# 35x35.net
KiCad netlist of a schematic drawn in EAGLE
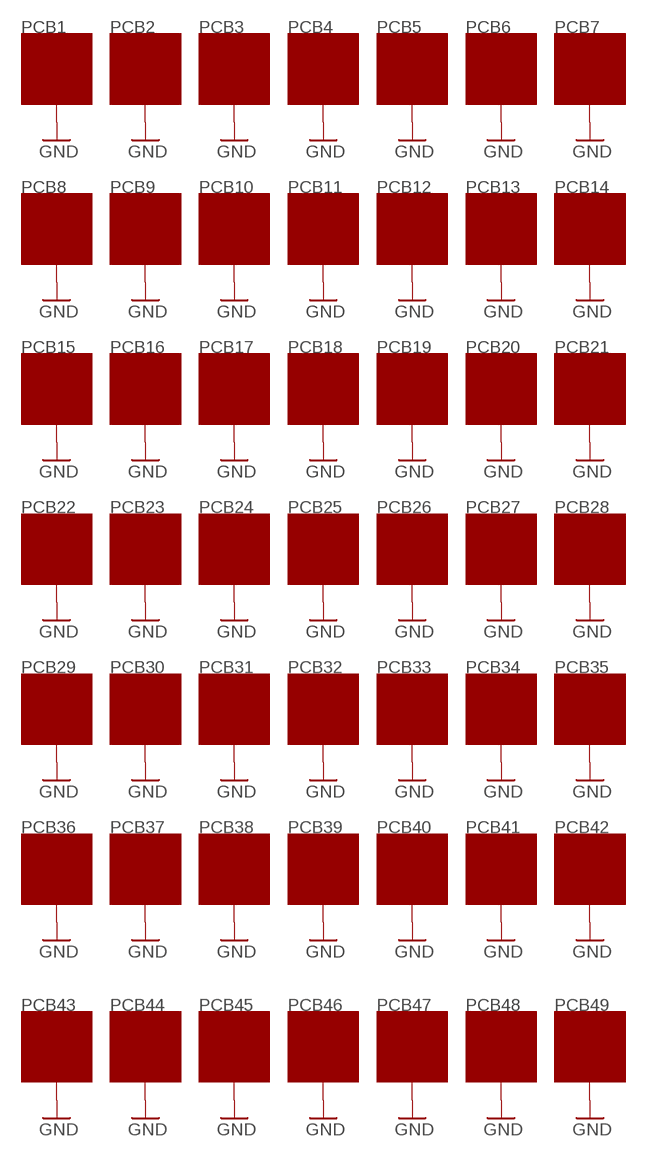
[diagram p0: schematic, sheet 1]

(export (version "E")
  (design (tool "Eeschema 10.0.6"))
  (components
    (comp (ref "PCB1")
      (value "ZZZ_MODULE05X05")
      (footprint "eagle-import:ZZZ_MODULE_05X05")
      (libsource (lib "eagle-import") (part "ZZZ_MODULE05X05"))
    )
    (comp (ref "PCB2")
      (value "ZZZ_MODULE05X05")
      (footprint "eagle-import:ZZZ_MODULE_05X05")
      (libsource (lib "eagle-import") (part "ZZZ_MODULE05X05"))
    )
    (comp (ref "PCB3")
      (value "ZZZ_MODULE05X05")
      (footprint "eagle-import:ZZZ_MODULE_05X05")
      (libsource (lib "eagle-import") (part "ZZZ_MODULE05X05"))
    )
    (comp (ref "PCB4")
      (value "ZZZ_MODULE05X05")
      (footprint "eagle-import:ZZZ_MODULE_05X05")
      (libsource (lib "eagle-import") (part "ZZZ_MODULE05X05"))
    )
    (comp (ref "PCB5")
      (value "ZZZ_MODULE05X05")
      (footprint "eagle-import:ZZZ_MODULE_05X05")
      (libsource (lib "eagle-import") (part "ZZZ_MODULE05X05"))
    )
    (comp (ref "PCB6")
      (value "ZZZ_MODULE05X05")
      (footprint "eagle-import:ZZZ_MODULE_05X05")
      (libsource (lib "eagle-import") (part "ZZZ_MODULE05X05"))
    )
    (comp (ref "PCB7")
      (value "ZZZ_MODULE05X05")
      (footprint "eagle-import:ZZZ_MODULE_05X05")
      (libsource (lib "eagle-import") (part "ZZZ_MODULE05X05"))
    )
    (comp (ref "PCB8")
      (value "ZZZ_MODULE05X05")
      (footprint "eagle-import:ZZZ_MODULE_05X05")
      (libsource (lib "eagle-import") (part "ZZZ_MODULE05X05"))
    )
    (comp (ref "PCB9")
      (value "ZZZ_MODULE05X05")
      (footprint "eagle-import:ZZZ_MODULE_05X05")
      (libsource (lib "eagle-import") (part "ZZZ_MODULE05X05"))
    )
    (comp (ref "PCB10")
      (value "ZZZ_MODULE05X05")
      (footprint "eagle-import:ZZZ_MODULE_05X05")
      (libsource (lib "eagle-import") (part "ZZZ_MODULE05X05"))
    )
    (comp (ref "PCB11")
      (value "ZZZ_MODULE05X05")
      (footprint "eagle-import:ZZZ_MODULE_05X05")
      (libsource (lib "eagle-import") (part "ZZZ_MODULE05X05"))
    )
    (comp (ref "PCB12")
      (value "ZZZ_MODULE05X05")
      (footprint "eagle-import:ZZZ_MODULE_05X05")
      (libsource (lib "eagle-import") (part "ZZZ_MODULE05X05"))
    )
    (comp (ref "PCB13")
      (value "ZZZ_MODULE05X05")
      (footprint "eagle-import:ZZZ_MODULE_05X05")
      (libsource (lib "eagle-import") (part "ZZZ_MODULE05X05"))
    )
    (comp (ref "PCB14")
      (value "ZZZ_MODULE05X05")
      (footprint "eagle-import:ZZZ_MODULE_05X05")
      (libsource (lib "eagle-import") (part "ZZZ_MODULE05X05"))
    )
    (comp (ref "PCB15")
      (value "ZZZ_MODULE05X05")
      (footprint "eagle-import:ZZZ_MODULE_05X05")
      (libsource (lib "eagle-import") (part "ZZZ_MODULE05X05"))
    )
    (comp (ref "PCB16")
      (value "ZZZ_MODULE05X05")
      (footprint "eagle-import:ZZZ_MODULE_05X05")
      (libsource (lib "eagle-import") (part "ZZZ_MODULE05X05"))
    )
    (comp (ref "PCB17")
      (value "ZZZ_MODULE05X05")
      (footprint "eagle-import:ZZZ_MODULE_05X05")
      (libsource (lib "eagle-import") (part "ZZZ_MODULE05X05"))
    )
    (comp (ref "PCB18")
      (value "ZZZ_MODULE05X05")
      (footprint "eagle-import:ZZZ_MODULE_05X05")
      (libsource (lib "eagle-import") (part "ZZZ_MODULE05X05"))
    )
    (comp (ref "PCB19")
      (value "ZZZ_MODULE05X05")
      (footprint "eagle-import:ZZZ_MODULE_05X05")
      (libsource (lib "eagle-import") (part "ZZZ_MODULE05X05"))
    )
    (comp (ref "PCB20")
      (value "ZZZ_MODULE05X05")
      (footprint "eagle-import:ZZZ_MODULE_05X05")
      (libsource (lib "eagle-import") (part "ZZZ_MODULE05X05"))
    )
    (comp (ref "PCB21")
      (value "ZZZ_MODULE05X05")
      (footprint "eagle-import:ZZZ_MODULE_05X05")
      (libsource (lib "eagle-import") (part "ZZZ_MODULE05X05"))
    )
    (comp (ref "PCB22")
      (value "ZZZ_MODULE05X05")
      (footprint "eagle-import:ZZZ_MODULE_05X05")
      (libsource (lib "eagle-import") (part "ZZZ_MODULE05X05"))
    )
    (comp (ref "PCB23")
      (value "ZZZ_MODULE05X05")
      (footprint "eagle-import:ZZZ_MODULE_05X05")
      (libsource (lib "eagle-import") (part "ZZZ_MODULE05X05"))
    )
    (comp (ref "PCB24")
      (value "ZZZ_MODULE05X05")
      (footprint "eagle-import:ZZZ_MODULE_05X05")
      (libsource (lib "eagle-import") (part "ZZZ_MODULE05X05"))
    )
    (comp (ref "PCB25")
      (value "ZZZ_MODULE05X05")
      (footprint "eagle-import:ZZZ_MODULE_05X05")
      (libsource (lib "eagle-import") (part "ZZZ_MODULE05X05"))
    )
    (comp (ref "PCB26")
      (value "ZZZ_MODULE05X05")
      (footprint "eagle-import:ZZZ_MODULE_05X05")
      (libsource (lib "eagle-import") (part "ZZZ_MODULE05X05"))
    )
    (comp (ref "PCB27")
      (value "ZZZ_MODULE05X05")
      (footprint "eagle-import:ZZZ_MODULE_05X05")
      (libsource (lib "eagle-import") (part "ZZZ_MODULE05X05"))
    )
    (comp (ref "PCB28")
      (value "ZZZ_MODULE05X05")
      (footprint "eagle-import:ZZZ_MODULE_05X05")
      (libsource (lib "eagle-import") (part "ZZZ_MODULE05X05"))
    )
    (comp (ref "PCB29")
      (value "ZZZ_MODULE05X05")
      (footprint "eagle-import:ZZZ_MODULE_05X05")
      (libsource (lib "eagle-import") (part "ZZZ_MODULE05X05"))
    )
    (comp (ref "PCB30")
      (value "ZZZ_MODULE05X05")
      (footprint "eagle-import:ZZZ_MODULE_05X05")
      (libsource (lib "eagle-import") (part "ZZZ_MODULE05X05"))
    )
    (comp (ref "PCB31")
      (value "ZZZ_MODULE05X05")
      (footprint "eagle-import:ZZZ_MODULE_05X05")
      (libsource (lib "eagle-import") (part "ZZZ_MODULE05X05"))
    )
    (comp (ref "PCB32")
      (value "ZZZ_MODULE05X05")
      (footprint "eagle-import:ZZZ_MODULE_05X05")
      (libsource (lib "eagle-import") (part "ZZZ_MODULE05X05"))
    )
    (comp (ref "PCB33")
      (value "ZZZ_MODULE05X05")
      (footprint "eagle-import:ZZZ_MODULE_05X05")
      (libsource (lib "eagle-import") (part "ZZZ_MODULE05X05"))
    )
    (comp (ref "PCB34")
      (value "ZZZ_MODULE05X05")
      (footprint "eagle-import:ZZZ_MODULE_05X05")
      (libsource (lib "eagle-import") (part "ZZZ_MODULE05X05"))
    )
    (comp (ref "PCB35")
      (value "ZZZ_MODULE05X05")
      (footprint "eagle-import:ZZZ_MODULE_05X05")
      (libsource (lib "eagle-import") (part "ZZZ_MODULE05X05"))
    )
    (comp (ref "PCB36")
      (value "ZZZ_MODULE05X05")
      (footprint "eagle-import:ZZZ_MODULE_05X05")
      (libsource (lib "eagle-import") (part "ZZZ_MODULE05X05"))
    )
    (comp (ref "PCB37")
      (value "ZZZ_MODULE05X05")
      (footprint "eagle-import:ZZZ_MODULE_05X05")
      (libsource (lib "eagle-import") (part "ZZZ_MODULE05X05"))
    )
    (comp (ref "PCB38")
      (value "ZZZ_MODULE05X05")
      (footprint "eagle-import:ZZZ_MODULE_05X05")
      (libsource (lib "eagle-import") (part "ZZZ_MODULE05X05"))
    )
    (comp (ref "PCB39")
      (value "ZZZ_MODULE05X05")
      (footprint "eagle-import:ZZZ_MODULE_05X05")
      (libsource (lib "eagle-import") (part "ZZZ_MODULE05X05"))
    )
    (comp (ref "PCB40")
      (value "ZZZ_MODULE05X05")
      (footprint "eagle-import:ZZZ_MODULE_05X05")
      (libsource (lib "eagle-import") (part "ZZZ_MODULE05X05"))
    )
    (comp (ref "PCB41")
      (value "ZZZ_MODULE05X05")
      (footprint "eagle-import:ZZZ_MODULE_05X05")
      (libsource (lib "eagle-import") (part "ZZZ_MODULE05X05"))
    )
    (comp (ref "PCB42")
      (value "ZZZ_MODULE05X05")
      (footprint "eagle-import:ZZZ_MODULE_05X05")
      (libsource (lib "eagle-import") (part "ZZZ_MODULE05X05"))
    )
    (comp (ref "PCB43")
      (value "ZZZ_MODULE05X05")
      (footprint "eagle-import:ZZZ_MODULE_05X05")
      (libsource (lib "eagle-import") (part "ZZZ_MODULE05X05"))
    )
    (comp (ref "PCB44")
      (value "ZZZ_MODULE05X05")
      (footprint "eagle-import:ZZZ_MODULE_05X05")
      (libsource (lib "eagle-import") (part "ZZZ_MODULE05X05"))
    )
    (comp (ref "PCB45")
      (value "ZZZ_MODULE05X05")
      (footprint "eagle-import:ZZZ_MODULE_05X05")
      (libsource (lib "eagle-import") (part "ZZZ_MODULE05X05"))
    )
    (comp (ref "PCB46")
      (value "ZZZ_MODULE05X05")
      (footprint "eagle-import:ZZZ_MODULE_05X05")
      (libsource (lib "eagle-import") (part "ZZZ_MODULE05X05"))
    )
    (comp (ref "PCB47")
      (value "ZZZ_MODULE05X05")
      (footprint "eagle-import:ZZZ_MODULE_05X05")
      (libsource (lib "eagle-import") (part "ZZZ_MODULE05X05"))
    )
    (comp (ref "PCB48")
      (value "ZZZ_MODULE05X05")
      (footprint "eagle-import:ZZZ_MODULE_05X05")
      (libsource (lib "eagle-import") (part "ZZZ_MODULE05X05"))
    )
    (comp (ref "PCB49")
      (value "ZZZ_MODULE05X05")
      (footprint "eagle-import:ZZZ_MODULE_05X05")
      (libsource (lib "eagle-import") (part "ZZZ_MODULE05X05"))
    )
  )
  (nets
    (net (code "1") (name "GND") (class "Default")
      (node (ref "PCB1") (pin "GND@1") (pinfunction "GND_GND@1") (pintype "power_in"))
      (node (ref "PCB1") (pin "GND@2") (pinfunction "GND_GND@2") (pintype "power_in"))
      (node (ref "PCB1") (pin "GND@3") (pinfunction "GND_GND@3") (pintype "power_in"))
      (node (ref "PCB1") (pin "GND@4") (pinfunction "GND_GND@4") (pintype "power_in"))
      (node (ref "PCB1") (pin "GND@5") (pinfunction "GND_GND@5") (pintype "power_in"))
      (node (ref "PCB1") (pin "GND@6") (pinfunction "GND_GND@6") (pintype "power_in"))
      (node (ref "PCB1") (pin "GND@7") (pinfunction "GND_GND@7") (pintype "power_in"))
      (node (ref "PCB1") (pin "GND@8") (pinfunction "GND_GND@8") (pintype "power_in"))
      (node (ref "PCB10") (pin "GND@1") (pinfunction "GND_GND@1") (pintype "power_in"))
      (node (ref "PCB10") (pin "GND@2") (pinfunction "GND_GND@2") (pintype "power_in"))
      (node (ref "PCB10") (pin "GND@3") (pinfunction "GND_GND@3") (pintype "power_in"))
      (node (ref "PCB10") (pin "GND@4") (pinfunction "GND_GND@4") (pintype "power_in"))
      (node (ref "PCB10") (pin "GND@5") (pinfunction "GND_GND@5") (pintype "power_in"))
      (node (ref "PCB10") (pin "GND@6") (pinfunction "GND_GND@6") (pintype "power_in"))
      (node (ref "PCB10") (pin "GND@7") (pinfunction "GND_GND@7") (pintype "power_in"))
      (node (ref "PCB10") (pin "GND@8") (pinfunction "GND_GND@8") (pintype "power_in"))
      (node (ref "PCB11") (pin "GND@1") (pinfunction "GND_GND@1") (pintype "power_in"))
      (node (ref "PCB11") (pin "GND@2") (pinfunction "GND_GND@2") (pintype "power_in"))
      (node (ref "PCB11") (pin "GND@3") (pinfunction "GND_GND@3") (pintype "power_in"))
      (node (ref "PCB11") (pin "GND@4") (pinfunction "GND_GND@4") (pintype "power_in"))
      (node (ref "PCB11") (pin "GND@5") (pinfunction "GND_GND@5") (pintype "power_in"))
      (node (ref "PCB11") (pin "GND@6") (pinfunction "GND_GND@6") (pintype "power_in"))
      (node (ref "PCB11") (pin "GND@7") (pinfunction "GND_GND@7") (pintype "power_in"))
      (node (ref "PCB11") (pin "GND@8") (pinfunction "GND_GND@8") (pintype "power_in"))
      (node (ref "PCB12") (pin "GND@1") (pinfunction "GND_GND@1") (pintype "power_in"))
      (node (ref "PCB12") (pin "GND@2") (pinfunction "GND_GND@2") (pintype "power_in"))
      (node (ref "PCB12") (pin "GND@3") (pinfunction "GND_GND@3") (pintype "power_in"))
      (node (ref "PCB12") (pin "GND@4") (pinfunction "GND_GND@4") (pintype "power_in"))
      (node (ref "PCB12") (pin "GND@5") (pinfunction "GND_GND@5") (pintype "power_in"))
      (node (ref "PCB12") (pin "GND@6") (pinfunction "GND_GND@6") (pintype "power_in"))
      (node (ref "PCB12") (pin "GND@7") (pinfunction "GND_GND@7") (pintype "power_in"))
      (node (ref "PCB12") (pin "GND@8") (pinfunction "GND_GND@8") (pintype "power_in"))
      (node (ref "PCB13") (pin "GND@1") (pinfunction "GND_GND@1") (pintype "power_in"))
      (node (ref "PCB13") (pin "GND@2") (pinfunction "GND_GND@2") (pintype "power_in"))
      (node (ref "PCB13") (pin "GND@3") (pinfunction "GND_GND@3") (pintype "power_in"))
      (node (ref "PCB13") (pin "GND@4") (pinfunction "GND_GND@4") (pintype "power_in"))
      (node (ref "PCB13") (pin "GND@5") (pinfunction "GND_GND@5") (pintype "power_in"))
      (node (ref "PCB13") (pin "GND@6") (pinfunction "GND_GND@6") (pintype "power_in"))
      (node (ref "PCB13") (pin "GND@7") (pinfunction "GND_GND@7") (pintype "power_in"))
      (node (ref "PCB13") (pin "GND@8") (pinfunction "GND_GND@8") (pintype "power_in"))
      (node (ref "PCB14") (pin "GND@1") (pinfunction "GND_GND@1") (pintype "power_in"))
      (node (ref "PCB14") (pin "GND@2") (pinfunction "GND_GND@2") (pintype "power_in"))
      (node (ref "PCB14") (pin "GND@3") (pinfunction "GND_GND@3") (pintype "power_in"))
      (node (ref "PCB14") (pin "GND@4") (pinfunction "GND_GND@4") (pintype "power_in"))
      (node (ref "PCB14") (pin "GND@5") (pinfunction "GND_GND@5") (pintype "power_in"))
      (node (ref "PCB14") (pin "GND@6") (pinfunction "GND_GND@6") (pintype "power_in"))
      (node (ref "PCB14") (pin "GND@7") (pinfunction "GND_GND@7") (pintype "power_in"))
      (node (ref "PCB14") (pin "GND@8") (pinfunction "GND_GND@8") (pintype "power_in"))
      (node (ref "PCB15") (pin "GND@1") (pinfunction "GND_GND@1") (pintype "power_in"))
      (node (ref "PCB15") (pin "GND@2") (pinfunction "GND_GND@2") (pintype "power_in"))
      (node (ref "PCB15") (pin "GND@3") (pinfunction "GND_GND@3") (pintype "power_in"))
      (node (ref "PCB15") (pin "GND@4") (pinfunction "GND_GND@4") (pintype "power_in"))
      (node (ref "PCB15") (pin "GND@5") (pinfunction "GND_GND@5") (pintype "power_in"))
      (node (ref "PCB15") (pin "GND@6") (pinfunction "GND_GND@6") (pintype "power_in"))
      (node (ref "PCB15") (pin "GND@7") (pinfunction "GND_GND@7") (pintype "power_in"))
      (node (ref "PCB15") (pin "GND@8") (pinfunction "GND_GND@8") (pintype "power_in"))
      (node (ref "PCB16") (pin "GND@1") (pinfunction "GND_GND@1") (pintype "power_in"))
      (node (ref "PCB16") (pin "GND@2") (pinfunction "GND_GND@2") (pintype "power_in"))
      (node (ref "PCB16") (pin "GND@3") (pinfunction "GND_GND@3") (pintype "power_in"))
      (node (ref "PCB16") (pin "GND@4") (pinfunction "GND_GND@4") (pintype "power_in"))
      (node (ref "PCB16") (pin "GND@5") (pinfunction "GND_GND@5") (pintype "power_in"))
      (node (ref "PCB16") (pin "GND@6") (pinfunction "GND_GND@6") (pintype "power_in"))
      (node (ref "PCB16") (pin "GND@7") (pinfunction "GND_GND@7") (pintype "power_in"))
      (node (ref "PCB16") (pin "GND@8") (pinfunction "GND_GND@8") (pintype "power_in"))
      (node (ref "PCB17") (pin "GND@1") (pinfunction "GND_GND@1") (pintype "power_in"))
      (node (ref "PCB17") (pin "GND@2") (pinfunction "GND_GND@2") (pintype "power_in"))
      (node (ref "PCB17") (pin "GND@3") (pinfunction "GND_GND@3") (pintype "power_in"))
      (node (ref "PCB17") (pin "GND@4") (pinfunction "GND_GND@4") (pintype "power_in"))
      (node (ref "PCB17") (pin "GND@5") (pinfunction "GND_GND@5") (pintype "power_in"))
      (node (ref "PCB17") (pin "GND@6") (pinfunction "GND_GND@6") (pintype "power_in"))
      (node (ref "PCB17") (pin "GND@7") (pinfunction "GND_GND@7") (pintype "power_in"))
      (node (ref "PCB17") (pin "GND@8") (pinfunction "GND_GND@8") (pintype "power_in"))
      (node (ref "PCB18") (pin "GND@1") (pinfunction "GND_GND@1") (pintype "power_in"))
      (node (ref "PCB18") (pin "GND@2") (pinfunction "GND_GND@2") (pintype "power_in"))
      (node (ref "PCB18") (pin "GND@3") (pinfunction "GND_GND@3") (pintype "power_in"))
      (node (ref "PCB18") (pin "GND@4") (pinfunction "GND_GND@4") (pintype "power_in"))
      (node (ref "PCB18") (pin "GND@5") (pinfunction "GND_GND@5") (pintype "power_in"))
      (node (ref "PCB18") (pin "GND@6") (pinfunction "GND_GND@6") (pintype "power_in"))
      (node (ref "PCB18") (pin "GND@7") (pinfunction "GND_GND@7") (pintype "power_in"))
      (node (ref "PCB18") (pin "GND@8") (pinfunction "GND_GND@8") (pintype "power_in"))
      (node (ref "PCB19") (pin "GND@1") (pinfunction "GND_GND@1") (pintype "power_in"))
      (node (ref "PCB19") (pin "GND@2") (pinfunction "GND_GND@2") (pintype "power_in"))
      (node (ref "PCB19") (pin "GND@3") (pinfunction "GND_GND@3") (pintype "power_in"))
      (node (ref "PCB19") (pin "GND@4") (pinfunction "GND_GND@4") (pintype "power_in"))
      (node (ref "PCB19") (pin "GND@5") (pinfunction "GND_GND@5") (pintype "power_in"))
      (node (ref "PCB19") (pin "GND@6") (pinfunction "GND_GND@6") (pintype "power_in"))
      (node (ref "PCB19") (pin "GND@7") (pinfunction "GND_GND@7") (pintype "power_in"))
      (node (ref "PCB19") (pin "GND@8") (pinfunction "GND_GND@8") (pintype "power_in"))
      (node (ref "PCB2") (pin "GND@1") (pinfunction "GND_GND@1") (pintype "power_in"))
      (node (ref "PCB2") (pin "GND@2") (pinfunction "GND_GND@2") (pintype "power_in"))
      (node (ref "PCB2") (pin "GND@3") (pinfunction "GND_GND@3") (pintype "power_in"))
      (node (ref "PCB2") (pin "GND@4") (pinfunction "GND_GND@4") (pintype "power_in"))
      (node (ref "PCB2") (pin "GND@5") (pinfunction "GND_GND@5") (pintype "power_in"))
      (node (ref "PCB2") (pin "GND@6") (pinfunction "GND_GND@6") (pintype "power_in"))
      (node (ref "PCB2") (pin "GND@7") (pinfunction "GND_GND@7") (pintype "power_in"))
      (node (ref "PCB2") (pin "GND@8") (pinfunction "GND_GND@8") (pintype "power_in"))
      (node (ref "PCB20") (pin "GND@1") (pinfunction "GND_GND@1") (pintype "power_in"))
      (node (ref "PCB20") (pin "GND@2") (pinfunction "GND_GND@2") (pintype "power_in"))
      (node (ref "PCB20") (pin "GND@3") (pinfunction "GND_GND@3") (pintype "power_in"))
      (node (ref "PCB20") (pin "GND@4") (pinfunction "GND_GND@4") (pintype "power_in"))
      (node (ref "PCB20") (pin "GND@5") (pinfunction "GND_GND@5") (pintype "power_in"))
      (node (ref "PCB20") (pin "GND@6") (pinfunction "GND_GND@6") (pintype "power_in"))
      (node (ref "PCB20") (pin "GND@7") (pinfunction "GND_GND@7") (pintype "power_in"))
      (node (ref "PCB20") (pin "GND@8") (pinfunction "GND_GND@8") (pintype "power_in"))
      (node (ref "PCB21") (pin "GND@1") (pinfunction "GND_GND@1") (pintype "power_in"))
      (node (ref "PCB21") (pin "GND@2") (pinfunction "GND_GND@2") (pintype "power_in"))
      (node (ref "PCB21") (pin "GND@3") (pinfunction "GND_GND@3") (pintype "power_in"))
      (node (ref "PCB21") (pin "GND@4") (pinfunction "GND_GND@4") (pintype "power_in"))
      (node (ref "PCB21") (pin "GND@5") (pinfunction "GND_GND@5") (pintype "power_in"))
      (node (ref "PCB21") (pin "GND@6") (pinfunction "GND_GND@6") (pintype "power_in"))
      (node (ref "PCB21") (pin "GND@7") (pinfunction "GND_GND@7") (pintype "power_in"))
      (node (ref "PCB21") (pin "GND@8") (pinfunction "GND_GND@8") (pintype "power_in"))
      (node (ref "PCB22") (pin "GND@1") (pinfunction "GND_GND@1") (pintype "power_in"))
      (node (ref "PCB22") (pin "GND@2") (pinfunction "GND_GND@2") (pintype "power_in"))
      (node (ref "PCB22") (pin "GND@3") (pinfunction "GND_GND@3") (pintype "power_in"))
      (node (ref "PCB22") (pin "GND@4") (pinfunction "GND_GND@4") (pintype "power_in"))
      (node (ref "PCB22") (pin "GND@5") (pinfunction "GND_GND@5") (pintype "power_in"))
      (node (ref "PCB22") (pin "GND@6") (pinfunction "GND_GND@6") (pintype "power_in"))
      (node (ref "PCB22") (pin "GND@7") (pinfunction "GND_GND@7") (pintype "power_in"))
      (node (ref "PCB22") (pin "GND@8") (pinfunction "GND_GND@8") (pintype "power_in"))
      (node (ref "PCB23") (pin "GND@1") (pinfunction "GND_GND@1") (pintype "power_in"))
      (node (ref "PCB23") (pin "GND@2") (pinfunction "GND_GND@2") (pintype "power_in"))
      (node (ref "PCB23") (pin "GND@3") (pinfunction "GND_GND@3") (pintype "power_in"))
      (node (ref "PCB23") (pin "GND@4") (pinfunction "GND_GND@4") (pintype "power_in"))
      (node (ref "PCB23") (pin "GND@5") (pinfunction "GND_GND@5") (pintype "power_in"))
      (node (ref "PCB23") (pin "GND@6") (pinfunction "GND_GND@6") (pintype "power_in"))
      (node (ref "PCB23") (pin "GND@7") (pinfunction "GND_GND@7") (pintype "power_in"))
      (node (ref "PCB23") (pin "GND@8") (pinfunction "GND_GND@8") (pintype "power_in"))
      (node (ref "PCB24") (pin "GND@1") (pinfunction "GND_GND@1") (pintype "power_in"))
      (node (ref "PCB24") (pin "GND@2") (pinfunction "GND_GND@2") (pintype "power_in"))
      (node (ref "PCB24") (pin "GND@3") (pinfunction "GND_GND@3") (pintype "power_in"))
      (node (ref "PCB24") (pin "GND@4") (pinfunction "GND_GND@4") (pintype "power_in"))
      (node (ref "PCB24") (pin "GND@5") (pinfunction "GND_GND@5") (pintype "power_in"))
      (node (ref "PCB24") (pin "GND@6") (pinfunction "GND_GND@6") (pintype "power_in"))
      (node (ref "PCB24") (pin "GND@7") (pinfunction "GND_GND@7") (pintype "power_in"))
      (node (ref "PCB24") (pin "GND@8") (pinfunction "GND_GND@8") (pintype "power_in"))
      (node (ref "PCB25") (pin "GND@1") (pinfunction "GND_GND@1") (pintype "power_in"))
      (node (ref "PCB25") (pin "GND@2") (pinfunction "GND_GND@2") (pintype "power_in"))
      (node (ref "PCB25") (pin "GND@3") (pinfunction "GND_GND@3") (pintype "power_in"))
      (node (ref "PCB25") (pin "GND@4") (pinfunction "GND_GND@4") (pintype "power_in"))
      (node (ref "PCB25") (pin "GND@5") (pinfunction "GND_GND@5") (pintype "power_in"))
      (node (ref "PCB25") (pin "GND@6") (pinfunction "GND_GND@6") (pintype "power_in"))
      (node (ref "PCB25") (pin "GND@7") (pinfunction "GND_GND@7") (pintype "power_in"))
      (node (ref "PCB25") (pin "GND@8") (pinfunction "GND_GND@8") (pintype "power_in"))
      (node (ref "PCB26") (pin "GND@1") (pinfunction "GND_GND@1") (pintype "power_in"))
      (node (ref "PCB26") (pin "GND@2") (pinfunction "GND_GND@2") (pintype "power_in"))
      (node (ref "PCB26") (pin "GND@3") (pinfunction "GND_GND@3") (pintype "power_in"))
      (node (ref "PCB26") (pin "GND@4") (pinfunction "GND_GND@4") (pintype "power_in"))
      (node (ref "PCB26") (pin "GND@5") (pinfunction "GND_GND@5") (pintype "power_in"))
      (node (ref "PCB26") (pin "GND@6") (pinfunction "GND_GND@6") (pintype "power_in"))
      (node (ref "PCB26") (pin "GND@7") (pinfunction "GND_GND@7") (pintype "power_in"))
      (node (ref "PCB26") (pin "GND@8") (pinfunction "GND_GND@8") (pintype "power_in"))
      (node (ref "PCB27") (pin "GND@1") (pinfunction "GND_GND@1") (pintype "power_in"))
      (node (ref "PCB27") (pin "GND@2") (pinfunction "GND_GND@2") (pintype "power_in"))
      (node (ref "PCB27") (pin "GND@3") (pinfunction "GND_GND@3") (pintype "power_in"))
      (node (ref "PCB27") (pin "GND@4") (pinfunction "GND_GND@4") (pintype "power_in"))
      (node (ref "PCB27") (pin "GND@5") (pinfunction "GND_GND@5") (pintype "power_in"))
      (node (ref "PCB27") (pin "GND@6") (pinfunction "GND_GND@6") (pintype "power_in"))
      (node (ref "PCB27") (pin "GND@7") (pinfunction "GND_GND@7") (pintype "power_in"))
      (node (ref "PCB27") (pin "GND@8") (pinfunction "GND_GND@8") (pintype "power_in"))
      (node (ref "PCB28") (pin "GND@1") (pinfunction "GND_GND@1") (pintype "power_in"))
      (node (ref "PCB28") (pin "GND@2") (pinfunction "GND_GND@2") (pintype "power_in"))
      (node (ref "PCB28") (pin "GND@3") (pinfunction "GND_GND@3") (pintype "power_in"))
      (node (ref "PCB28") (pin "GND@4") (pinfunction "GND_GND@4") (pintype "power_in"))
      (node (ref "PCB28") (pin "GND@5") (pinfunction "GND_GND@5") (pintype "power_in"))
      (node (ref "PCB28") (pin "GND@6") (pinfunction "GND_GND@6") (pintype "power_in"))
      (node (ref "PCB28") (pin "GND@7") (pinfunction "GND_GND@7") (pintype "power_in"))
      (node (ref "PCB28") (pin "GND@8") (pinfunction "GND_GND@8") (pintype "power_in"))
      (node (ref "PCB29") (pin "GND@1") (pinfunction "GND_GND@1") (pintype "power_in"))
      (node (ref "PCB29") (pin "GND@2") (pinfunction "GND_GND@2") (pintype "power_in"))
      (node (ref "PCB29") (pin "GND@3") (pinfunction "GND_GND@3") (pintype "power_in"))
      (node (ref "PCB29") (pin "GND@4") (pinfunction "GND_GND@4") (pintype "power_in"))
      (node (ref "PCB29") (pin "GND@5") (pinfunction "GND_GND@5") (pintype "power_in"))
      (node (ref "PCB29") (pin "GND@6") (pinfunction "GND_GND@6") (pintype "power_in"))
      (node (ref "PCB29") (pin "GND@7") (pinfunction "GND_GND@7") (pintype "power_in"))
      (node (ref "PCB29") (pin "GND@8") (pinfunction "GND_GND@8") (pintype "power_in"))
      (node (ref "PCB3") (pin "GND@1") (pinfunction "GND_GND@1") (pintype "power_in"))
      (node (ref "PCB3") (pin "GND@2") (pinfunction "GND_GND@2") (pintype "power_in"))
      (node (ref "PCB3") (pin "GND@3") (pinfunction "GND_GND@3") (pintype "power_in"))
      (node (ref "PCB3") (pin "GND@4") (pinfunction "GND_GND@4") (pintype "power_in"))
      (node (ref "PCB3") (pin "GND@5") (pinfunction "GND_GND@5") (pintype "power_in"))
      (node (ref "PCB3") (pin "GND@6") (pinfunction "GND_GND@6") (pintype "power_in"))
      (node (ref "PCB3") (pin "GND@7") (pinfunction "GND_GND@7") (pintype "power_in"))
      (node (ref "PCB3") (pin "GND@8") (pinfunction "GND_GND@8") (pintype "power_in"))
      (node (ref "PCB30") (pin "GND@1") (pinfunction "GND_GND@1") (pintype "power_in"))
      (node (ref "PCB30") (pin "GND@2") (pinfunction "GND_GND@2") (pintype "power_in"))
      (node (ref "PCB30") (pin "GND@3") (pinfunction "GND_GND@3") (pintype "power_in"))
      (node (ref "PCB30") (pin "GND@4") (pinfunction "GND_GND@4") (pintype "power_in"))
      (node (ref "PCB30") (pin "GND@5") (pinfunction "GND_GND@5") (pintype "power_in"))
      (node (ref "PCB30") (pin "GND@6") (pinfunction "GND_GND@6") (pintype "power_in"))
      (node (ref "PCB30") (pin "GND@7") (pinfunction "GND_GND@7") (pintype "power_in"))
      (node (ref "PCB30") (pin "GND@8") (pinfunction "GND_GND@8") (pintype "power_in"))
      (node (ref "PCB31") (pin "GND@1") (pinfunction "GND_GND@1") (pintype "power_in"))
      (node (ref "PCB31") (pin "GND@2") (pinfunction "GND_GND@2") (pintype "power_in"))
      (node (ref "PCB31") (pin "GND@3") (pinfunction "GND_GND@3") (pintype "power_in"))
      (node (ref "PCB31") (pin "GND@4") (pinfunction "GND_GND@4") (pintype "power_in"))
      (node (ref "PCB31") (pin "GND@5") (pinfunction "GND_GND@5") (pintype "power_in"))
      (node (ref "PCB31") (pin "GND@6") (pinfunction "GND_GND@6") (pintype "power_in"))
      (node (ref "PCB31") (pin "GND@7") (pinfunction "GND_GND@7") (pintype "power_in"))
      (node (ref "PCB31") (pin "GND@8") (pinfunction "GND_GND@8") (pintype "power_in"))
      (node (ref "PCB32") (pin "GND@1") (pinfunction "GND_GND@1") (pintype "power_in"))
      (node (ref "PCB32") (pin "GND@2") (pinfunction "GND_GND@2") (pintype "power_in"))
      (node (ref "PCB32") (pin "GND@3") (pinfunction "GND_GND@3") (pintype "power_in"))
      (node (ref "PCB32") (pin "GND@4") (pinfunction "GND_GND@4") (pintype "power_in"))
      (node (ref "PCB32") (pin "GND@5") (pinfunction "GND_GND@5") (pintype "power_in"))
      (node (ref "PCB32") (pin "GND@6") (pinfunction "GND_GND@6") (pintype "power_in"))
      (node (ref "PCB32") (pin "GND@7") (pinfunction "GND_GND@7") (pintype "power_in"))
      (node (ref "PCB32") (pin "GND@8") (pinfunction "GND_GND@8") (pintype "power_in"))
      (node (ref "PCB33") (pin "GND@1") (pinfunction "GND_GND@1") (pintype "power_in"))
      (node (ref "PCB33") (pin "GND@2") (pinfunction "GND_GND@2") (pintype "power_in"))
      (node (ref "PCB33") (pin "GND@3") (pinfunction "GND_GND@3") (pintype "power_in"))
      (node (ref "PCB33") (pin "GND@4") (pinfunction "GND_GND@4") (pintype "power_in"))
      (node (ref "PCB33") (pin "GND@5") (pinfunction "GND_GND@5") (pintype "power_in"))
      (node (ref "PCB33") (pin "GND@6") (pinfunction "GND_GND@6") (pintype "power_in"))
      (node (ref "PCB33") (pin "GND@7") (pinfunction "GND_GND@7") (pintype "power_in"))
      (node (ref "PCB33") (pin "GND@8") (pinfunction "GND_GND@8") (pintype "power_in"))
      (node (ref "PCB34") (pin "GND@1") (pinfunction "GND_GND@1") (pintype "power_in"))
      (node (ref "PCB34") (pin "GND@2") (pinfunction "GND_GND@2") (pintype "power_in"))
      (node (ref "PCB34") (pin "GND@3") (pinfunction "GND_GND@3") (pintype "power_in"))
      (node (ref "PCB34") (pin "GND@4") (pinfunction "GND_GND@4") (pintype "power_in"))
      (node (ref "PCB34") (pin "GND@5") (pinfunction "GND_GND@5") (pintype "power_in"))
      (node (ref "PCB34") (pin "GND@6") (pinfunction "GND_GND@6") (pintype "power_in"))
      (node (ref "PCB34") (pin "GND@7") (pinfunction "GND_GND@7") (pintype "power_in"))
      (node (ref "PCB34") (pin "GND@8") (pinfunction "GND_GND@8") (pintype "power_in"))
      (node (ref "PCB35") (pin "GND@1") (pinfunction "GND_GND@1") (pintype "power_in"))
      (node (ref "PCB35") (pin "GND@2") (pinfunction "GND_GND@2") (pintype "power_in"))
      (node (ref "PCB35") (pin "GND@3") (pinfunction "GND_GND@3") (pintype "power_in"))
      (node (ref "PCB35") (pin "GND@4") (pinfunction "GND_GND@4") (pintype "power_in"))
      (node (ref "PCB35") (pin "GND@5") (pinfunction "GND_GND@5") (pintype "power_in"))
      (node (ref "PCB35") (pin "GND@6") (pinfunction "GND_GND@6") (pintype "power_in"))
      (node (ref "PCB35") (pin "GND@7") (pinfunction "GND_GND@7") (pintype "power_in"))
      (node (ref "PCB35") (pin "GND@8") (pinfunction "GND_GND@8") (pintype "power_in"))
      (node (ref "PCB36") (pin "GND@1") (pinfunction "GND_GND@1") (pintype "power_in"))
      (node (ref "PCB36") (pin "GND@2") (pinfunction "GND_GND@2") (pintype "power_in"))
      (node (ref "PCB36") (pin "GND@3") (pinfunction "GND_GND@3") (pintype "power_in"))
      (node (ref "PCB36") (pin "GND@4") (pinfunction "GND_GND@4") (pintype "power_in"))
      (node (ref "PCB36") (pin "GND@5") (pinfunction "GND_GND@5") (pintype "power_in"))
      (node (ref "PCB36") (pin "GND@6") (pinfunction "GND_GND@6") (pintype "power_in"))
      (node (ref "PCB36") (pin "GND@7") (pinfunction "GND_GND@7") (pintype "power_in"))
      (node (ref "PCB36") (pin "GND@8") (pinfunction "GND_GND@8") (pintype "power_in"))
      (node (ref "PCB37") (pin "GND@1") (pinfunction "GND_GND@1") (pintype "power_in"))
      (node (ref "PCB37") (pin "GND@2") (pinfunction "GND_GND@2") (pintype "power_in"))
      (node (ref "PCB37") (pin "GND@3") (pinfunction "GND_GND@3") (pintype "power_in"))
      (node (ref "PCB37") (pin "GND@4") (pinfunction "GND_GND@4") (pintype "power_in"))
      (node (ref "PCB37") (pin "GND@5") (pinfunction "GND_GND@5") (pintype "power_in"))
      (node (ref "PCB37") (pin "GND@6") (pinfunction "GND_GND@6") (pintype "power_in"))
      (node (ref "PCB37") (pin "GND@7") (pinfunction "GND_GND@7") (pintype "power_in"))
      (node (ref "PCB37") (pin "GND@8") (pinfunction "GND_GND@8") (pintype "power_in"))
      (node (ref "PCB38") (pin "GND@1") (pinfunction "GND_GND@1") (pintype "power_in"))
      (node (ref "PCB38") (pin "GND@2") (pinfunction "GND_GND@2") (pintype "power_in"))
      (node (ref "PCB38") (pin "GND@3") (pinfunction "GND_GND@3") (pintype "power_in"))
      (node (ref "PCB38") (pin "GND@4") (pinfunction "GND_GND@4") (pintype "power_in"))
      (node (ref "PCB38") (pin "GND@5") (pinfunction "GND_GND@5") (pintype "power_in"))
      (node (ref "PCB38") (pin "GND@6") (pinfunction "GND_GND@6") (pintype "power_in"))
      (node (ref "PCB38") (pin "GND@7") (pinfunction "GND_GND@7") (pintype "power_in"))
      (node (ref "PCB38") (pin "GND@8") (pinfunction "GND_GND@8") (pintype "power_in"))
      (node (ref "PCB39") (pin "GND@1") (pinfunction "GND_GND@1") (pintype "power_in"))
      (node (ref "PCB39") (pin "GND@2") (pinfunction "GND_GND@2") (pintype "power_in"))
      (node (ref "PCB39") (pin "GND@3") (pinfunction "GND_GND@3") (pintype "power_in"))
      (node (ref "PCB39") (pin "GND@4") (pinfunction "GND_GND@4") (pintype "power_in"))
      (node (ref "PCB39") (pin "GND@5") (pinfunction "GND_GND@5") (pintype "power_in"))
      (node (ref "PCB39") (pin "GND@6") (pinfunction "GND_GND@6") (pintype "power_in"))
      (node (ref "PCB39") (pin "GND@7") (pinfunction "GND_GND@7") (pintype "power_in"))
      (node (ref "PCB39") (pin "GND@8") (pinfunction "GND_GND@8") (pintype "power_in"))
      (node (ref "PCB4") (pin "GND@1") (pinfunction "GND_GND@1") (pintype "power_in"))
      (node (ref "PCB4") (pin "GND@2") (pinfunction "GND_GND@2") (pintype "power_in"))
      (node (ref "PCB4") (pin "GND@3") (pinfunction "GND_GND@3") (pintype "power_in"))
      (node (ref "PCB4") (pin "GND@4") (pinfunction "GND_GND@4") (pintype "power_in"))
      (node (ref "PCB4") (pin "GND@5") (pinfunction "GND_GND@5") (pintype "power_in"))
      (node (ref "PCB4") (pin "GND@6") (pinfunction "GND_GND@6") (pintype "power_in"))
      (node (ref "PCB4") (pin "GND@7") (pinfunction "GND_GND@7") (pintype "power_in"))
      (node (ref "PCB4") (pin "GND@8") (pinfunction "GND_GND@8") (pintype "power_in"))
      (node (ref "PCB40") (pin "GND@1") (pinfunction "GND_GND@1") (pintype "power_in"))
      (node (ref "PCB40") (pin "GND@2") (pinfunction "GND_GND@2") (pintype "power_in"))
      (node (ref "PCB40") (pin "GND@3") (pinfunction "GND_GND@3") (pintype "power_in"))
      (node (ref "PCB40") (pin "GND@4") (pinfunction "GND_GND@4") (pintype "power_in"))
      (node (ref "PCB40") (pin "GND@5") (pinfunction "GND_GND@5") (pintype "power_in"))
      (node (ref "PCB40") (pin "GND@6") (pinfunction "GND_GND@6") (pintype "power_in"))
      (node (ref "PCB40") (pin "GND@7") (pinfunction "GND_GND@7") (pintype "power_in"))
      (node (ref "PCB40") (pin "GND@8") (pinfunction "GND_GND@8") (pintype "power_in"))
      (node (ref "PCB41") (pin "GND@1") (pinfunction "GND_GND@1") (pintype "power_in"))
      (node (ref "PCB41") (pin "GND@2") (pinfunction "GND_GND@2") (pintype "power_in"))
      (node (ref "PCB41") (pin "GND@3") (pinfunction "GND_GND@3") (pintype "power_in"))
      (node (ref "PCB41") (pin "GND@4") (pinfunction "GND_GND@4") (pintype "power_in"))
      (node (ref "PCB41") (pin "GND@5") (pinfunction "GND_GND@5") (pintype "power_in"))
      (node (ref "PCB41") (pin "GND@6") (pinfunction "GND_GND@6") (pintype "power_in"))
      (node (ref "PCB41") (pin "GND@7") (pinfunction "GND_GND@7") (pintype "power_in"))
      (node (ref "PCB41") (pin "GND@8") (pinfunction "GND_GND@8") (pintype "power_in"))
      (node (ref "PCB42") (pin "GND@1") (pinfunction "GND_GND@1") (pintype "power_in"))
      (node (ref "PCB42") (pin "GND@2") (pinfunction "GND_GND@2") (pintype "power_in"))
      (node (ref "PCB42") (pin "GND@3") (pinfunction "GND_GND@3") (pintype "power_in"))
      (node (ref "PCB42") (pin "GND@4") (pinfunction "GND_GND@4") (pintype "power_in"))
      (node (ref "PCB42") (pin "GND@5") (pinfunction "GND_GND@5") (pintype "power_in"))
      (node (ref "PCB42") (pin "GND@6") (pinfunction "GND_GND@6") (pintype "power_in"))
      (node (ref "PCB42") (pin "GND@7") (pinfunction "GND_GND@7") (pintype "power_in"))
      (node (ref "PCB42") (pin "GND@8") (pinfunction "GND_GND@8") (pintype "power_in"))
      (node (ref "PCB43") (pin "GND@1") (pinfunction "GND_GND@1") (pintype "power_in"))
      (node (ref "PCB43") (pin "GND@2") (pinfunction "GND_GND@2") (pintype "power_in"))
      (node (ref "PCB43") (pin "GND@3") (pinfunction "GND_GND@3") (pintype "power_in"))
      (node (ref "PCB43") (pin "GND@4") (pinfunction "GND_GND@4") (pintype "power_in"))
      (node (ref "PCB43") (pin "GND@5") (pinfunction "GND_GND@5") (pintype "power_in"))
      (node (ref "PCB43") (pin "GND@6") (pinfunction "GND_GND@6") (pintype "power_in"))
      (node (ref "PCB43") (pin "GND@7") (pinfunction "GND_GND@7") (pintype "power_in"))
      (node (ref "PCB43") (pin "GND@8") (pinfunction "GND_GND@8") (pintype "power_in"))
      (node (ref "PCB44") (pin "GND@1") (pinfunction "GND_GND@1") (pintype "power_in"))
      (node (ref "PCB44") (pin "GND@2") (pinfunction "GND_GND@2") (pintype "power_in"))
      (node (ref "PCB44") (pin "GND@3") (pinfunction "GND_GND@3") (pintype "power_in"))
      (node (ref "PCB44") (pin "GND@4") (pinfunction "GND_GND@4") (pintype "power_in"))
      (node (ref "PCB44") (pin "GND@5") (pinfunction "GND_GND@5") (pintype "power_in"))
      (node (ref "PCB44") (pin "GND@6") (pinfunction "GND_GND@6") (pintype "power_in"))
      (node (ref "PCB44") (pin "GND@7") (pinfunction "GND_GND@7") (pintype "power_in"))
      (node (ref "PCB44") (pin "GND@8") (pinfunction "GND_GND@8") (pintype "power_in"))
      (node (ref "PCB45") (pin "GND@1") (pinfunction "GND_GND@1") (pintype "power_in"))
      (node (ref "PCB45") (pin "GND@2") (pinfunction "GND_GND@2") (pintype "power_in"))
      (node (ref "PCB45") (pin "GND@3") (pinfunction "GND_GND@3") (pintype "power_in"))
      (node (ref "PCB45") (pin "GND@4") (pinfunction "GND_GND@4") (pintype "power_in"))
      (node (ref "PCB45") (pin "GND@5") (pinfunction "GND_GND@5") (pintype "power_in"))
      (node (ref "PCB45") (pin "GND@6") (pinfunction "GND_GND@6") (pintype "power_in"))
      (node (ref "PCB45") (pin "GND@7") (pinfunction "GND_GND@7") (pintype "power_in"))
      (node (ref "PCB45") (pin "GND@8") (pinfunction "GND_GND@8") (pintype "power_in"))
      (node (ref "PCB46") (pin "GND@1") (pinfunction "GND_GND@1") (pintype "power_in"))
      (node (ref "PCB46") (pin "GND@2") (pinfunction "GND_GND@2") (pintype "power_in"))
      (node (ref "PCB46") (pin "GND@3") (pinfunction "GND_GND@3") (pintype "power_in"))
      (node (ref "PCB46") (pin "GND@4") (pinfunction "GND_GND@4") (pintype "power_in"))
      (node (ref "PCB46") (pin "GND@5") (pinfunction "GND_GND@5") (pintype "power_in"))
      (node (ref "PCB46") (pin "GND@6") (pinfunction "GND_GND@6") (pintype "power_in"))
      (node (ref "PCB46") (pin "GND@7") (pinfunction "GND_GND@7") (pintype "power_in"))
      (node (ref "PCB46") (pin "GND@8") (pinfunction "GND_GND@8") (pintype "power_in"))
      (node (ref "PCB47") (pin "GND@1") (pinfunction "GND_GND@1") (pintype "power_in"))
      (node (ref "PCB47") (pin "GND@2") (pinfunction "GND_GND@2") (pintype "power_in"))
      (node (ref "PCB47") (pin "GND@3") (pinfunction "GND_GND@3") (pintype "power_in"))
      (node (ref "PCB47") (pin "GND@4") (pinfunction "GND_GND@4") (pintype "power_in"))
      (node (ref "PCB47") (pin "GND@5") (pinfunction "GND_GND@5") (pintype "power_in"))
      (node (ref "PCB47") (pin "GND@6") (pinfunction "GND_GND@6") (pintype "power_in"))
      (node (ref "PCB47") (pin "GND@7") (pinfunction "GND_GND@7") (pintype "power_in"))
      (node (ref "PCB47") (pin "GND@8") (pinfunction "GND_GND@8") (pintype "power_in"))
      (node (ref "PCB48") (pin "GND@1") (pinfunction "GND_GND@1") (pintype "power_in"))
      (node (ref "PCB48") (pin "GND@2") (pinfunction "GND_GND@2") (pintype "power_in"))
      (node (ref "PCB48") (pin "GND@3") (pinfunction "GND_GND@3") (pintype "power_in"))
      (node (ref "PCB48") (pin "GND@4") (pinfunction "GND_GND@4") (pintype "power_in"))
      (node (ref "PCB48") (pin "GND@5") (pinfunction "GND_GND@5") (pintype "power_in"))
      (node (ref "PCB48") (pin "GND@6") (pinfunction "GND_GND@6") (pintype "power_in"))
      (node (ref "PCB48") (pin "GND@7") (pinfunction "GND_GND@7") (pintype "power_in"))
      (node (ref "PCB48") (pin "GND@8") (pinfunction "GND_GND@8") (pintype "power_in"))
      (node (ref "PCB49") (pin "GND@1") (pinfunction "GND_GND@1") (pintype "power_in"))
      (node (ref "PCB49") (pin "GND@2") (pinfunction "GND_GND@2") (pintype "power_in"))
      (node (ref "PCB49") (pin "GND@3") (pinfunction "GND_GND@3") (pintype "power_in"))
      (node (ref "PCB49") (pin "GND@4") (pinfunction "GND_GND@4") (pintype "power_in"))
      (node (ref "PCB49") (pin "GND@5") (pinfunction "GND_GND@5") (pintype "power_in"))
      (node (ref "PCB49") (pin "GND@6") (pinfunction "GND_GND@6") (pintype "power_in"))
      (node (ref "PCB49") (pin "GND@7") (pinfunction "GND_GND@7") (pintype "power_in"))
      (node (ref "PCB49") (pin "GND@8") (pinfunction "GND_GND@8") (pintype "power_in"))
      (node (ref "PCB5") (pin "GND@1") (pinfunction "GND_GND@1") (pintype "power_in"))
      (node (ref "PCB5") (pin "GND@2") (pinfunction "GND_GND@2") (pintype "power_in"))
      (node (ref "PCB5") (pin "GND@3") (pinfunction "GND_GND@3") (pintype "power_in"))
      (node (ref "PCB5") (pin "GND@4") (pinfunction "GND_GND@4") (pintype "power_in"))
      (node (ref "PCB5") (pin "GND@5") (pinfunction "GND_GND@5") (pintype "power_in"))
      (node (ref "PCB5") (pin "GND@6") (pinfunction "GND_GND@6") (pintype "power_in"))
      (node (ref "PCB5") (pin "GND@7") (pinfunction "GND_GND@7") (pintype "power_in"))
      (node (ref "PCB5") (pin "GND@8") (pinfunction "GND_GND@8") (pintype "power_in"))
      (node (ref "PCB6") (pin "GND@1") (pinfunction "GND_GND@1") (pintype "power_in"))
      (node (ref "PCB6") (pin "GND@2") (pinfunction "GND_GND@2") (pintype "power_in"))
      (node (ref "PCB6") (pin "GND@3") (pinfunction "GND_GND@3") (pintype "power_in"))
      (node (ref "PCB6") (pin "GND@4") (pinfunction "GND_GND@4") (pintype "power_in"))
      (node (ref "PCB6") (pin "GND@5") (pinfunction "GND_GND@5") (pintype "power_in"))
      (node (ref "PCB6") (pin "GND@6") (pinfunction "GND_GND@6") (pintype "power_in"))
      (node (ref "PCB6") (pin "GND@7") (pinfunction "GND_GND@7") (pintype "power_in"))
      (node (ref "PCB6") (pin "GND@8") (pinfunction "GND_GND@8") (pintype "power_in"))
      (node (ref "PCB7") (pin "GND@1") (pinfunction "GND_GND@1") (pintype "power_in"))
      (node (ref "PCB7") (pin "GND@2") (pinfunction "GND_GND@2") (pintype "power_in"))
      (node (ref "PCB7") (pin "GND@3") (pinfunction "GND_GND@3") (pintype "power_in"))
      (node (ref "PCB7") (pin "GND@4") (pinfunction "GND_GND@4") (pintype "power_in"))
      (node (ref "PCB7") (pin "GND@5") (pinfunction "GND_GND@5") (pintype "power_in"))
      (node (ref "PCB7") (pin "GND@6") (pinfunction "GND_GND@6") (pintype "power_in"))
      (node (ref "PCB7") (pin "GND@7") (pinfunction "GND_GND@7") (pintype "power_in"))
      (node (ref "PCB7") (pin "GND@8") (pinfunction "GND_GND@8") (pintype "power_in"))
      (node (ref "PCB8") (pin "GND@1") (pinfunction "GND_GND@1") (pintype "power_in"))
      (node (ref "PCB8") (pin "GND@2") (pinfunction "GND_GND@2") (pintype "power_in"))
      (node (ref "PCB8") (pin "GND@3") (pinfunction "GND_GND@3") (pintype "power_in"))
      (node (ref "PCB8") (pin "GND@4") (pinfunction "GND_GND@4") (pintype "power_in"))
      (node (ref "PCB8") (pin "GND@5") (pinfunction "GND_GND@5") (pintype "power_in"))
      (node (ref "PCB8") (pin "GND@6") (pinfunction "GND_GND@6") (pintype "power_in"))
      (node (ref "PCB8") (pin "GND@7") (pinfunction "GND_GND@7") (pintype "power_in"))
      (node (ref "PCB8") (pin "GND@8") (pinfunction "GND_GND@8") (pintype "power_in"))
      (node (ref "PCB9") (pin "GND@1") (pinfunction "GND_GND@1") (pintype "power_in"))
      (node (ref "PCB9") (pin "GND@2") (pinfunction "GND_GND@2") (pintype "power_in"))
      (node (ref "PCB9") (pin "GND@3") (pinfunction "GND_GND@3") (pintype "power_in"))
      (node (ref "PCB9") (pin "GND@4") (pinfunction "GND_GND@4") (pintype "power_in"))
      (node (ref "PCB9") (pin "GND@5") (pinfunction "GND_GND@5") (pintype "power_in"))
      (node (ref "PCB9") (pin "GND@6") (pinfunction "GND_GND@6") (pintype "power_in"))
      (node (ref "PCB9") (pin "GND@7") (pinfunction "GND_GND@7") (pintype "power_in"))
      (node (ref "PCB9") (pin "GND@8") (pinfunction "GND_GND@8") (pintype "power_in"))
    )
  )
)
